# Analog_HC_Overcurrent_Redundancy.net
KiCad netlist of a schematic drawn in Altium Designer
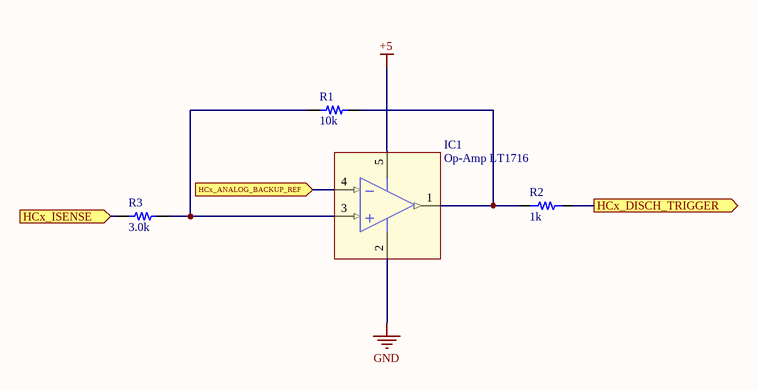
[diagram p0: Analog_HC_Overcurrent_Redundancy.SchDoc]

(export (version "E")
  (design (tool "Eeschema 10.0.6"))
  (components
    (comp (ref "IC1")
      (value "Op-Amp LT1716")
      (footprint "SOT23-5")
      (fields (field (name "MFRPARTNO") "LT1716IS5#PBF"))
      (libsource (lib "Altium-Lib") (part "Op-Amp LT1716"))
    )
    (comp (ref "R1")
      (value "10k")
      (footprint "RES 0603/1608")
      (fields
        (field (name "TOLERANCE") "1%")
        (field (name "POWER") "1/10W")
        (field (name "Comment") "Resistor 10k 0603 1/10W 1%")
        (field (name "CREATED_BY") "Nick Mah")
      )
      (libsource (lib "Altium-Lib") (part "Resistor"))
    )
    (comp (ref "R2")
      (value "1k")
      (footprint "RES 0805/2012")
      (fields
        (field (name "TOLERANCE") "1%")
        (field (name "POWER") "1/10W")
        (field (name "Comment") "Resistor 1k 0805 1/10W 1%")
        (field (name "CREATED_BY") "Nick Mah")
      )
      (libsource (lib "") (part "Resistor_1"))
    )
    (comp (ref "R3")
      (value "3.0k")
      (footprint "RES 0603/1608")
      (fields
        (field (name "TOLERANCE") "1%")
        (field (name "POWER") "1/10W")
        (field (name "Comment") "Resistor 3.0k 0603 1/10W 1%")
        (field (name "CREATED_BY") "Nick Mah")
      )
      (libsource (lib "Altium-Lib") (part "Resistor"))
    )
  )
  (nets
    (net (code "1") (name "+5") (class "Default")
      (node (ref "IC1") (pin "5") (pinfunction "V+_5") (pintype "power_in"))
    )
    (net (code "2") (name "/HCx_ANALOG_BACKUP_REF") (class "Default")
      (node (ref "IC1") (pin "4") (pinfunction "IN-_4") (pintype "input"))
    )
    (net (code "3") (name "/HCx_DISCH_TRIGGER") (class "Default")
      (node (ref "R2") (pin "2") (pinfunction "2_2") (pintype "passive"))
    )
    (net (code "4") (name "/HCx_ISENSE") (class "Default")
      (node (ref "R3") (pin "1") (pinfunction "1_1") (pintype "passive"))
    )
    (net (code "5") (name "GND") (class "Default")
      (node (ref "IC1") (pin "2") (pinfunction "V-_2") (pintype "power_in"))
    )
    (net (code "6") (name "Net-(IC1-IN+)") (class "Default")
      (node (ref "IC1") (pin "3") (pinfunction "IN+_3") (pintype "input"))
      (node (ref "R1") (pin "1") (pinfunction "1_1") (pintype "passive"))
      (node (ref "R3") (pin "2") (pinfunction "2_2") (pintype "passive"))
    )
    (net (code "7") (name "Net-(IC1-OUT)") (class "Default")
      (node (ref "IC1") (pin "1") (pinfunction "OUT_1") (pintype "output"))
      (node (ref "R1") (pin "2") (pinfunction "2_2") (pintype "passive"))
      (node (ref "R2") (pin "1") (pinfunction "1_1") (pintype "passive"))
    )
  )
)
